# MCU.net
KiCad netlist of a schematic drawn in Altium Designer
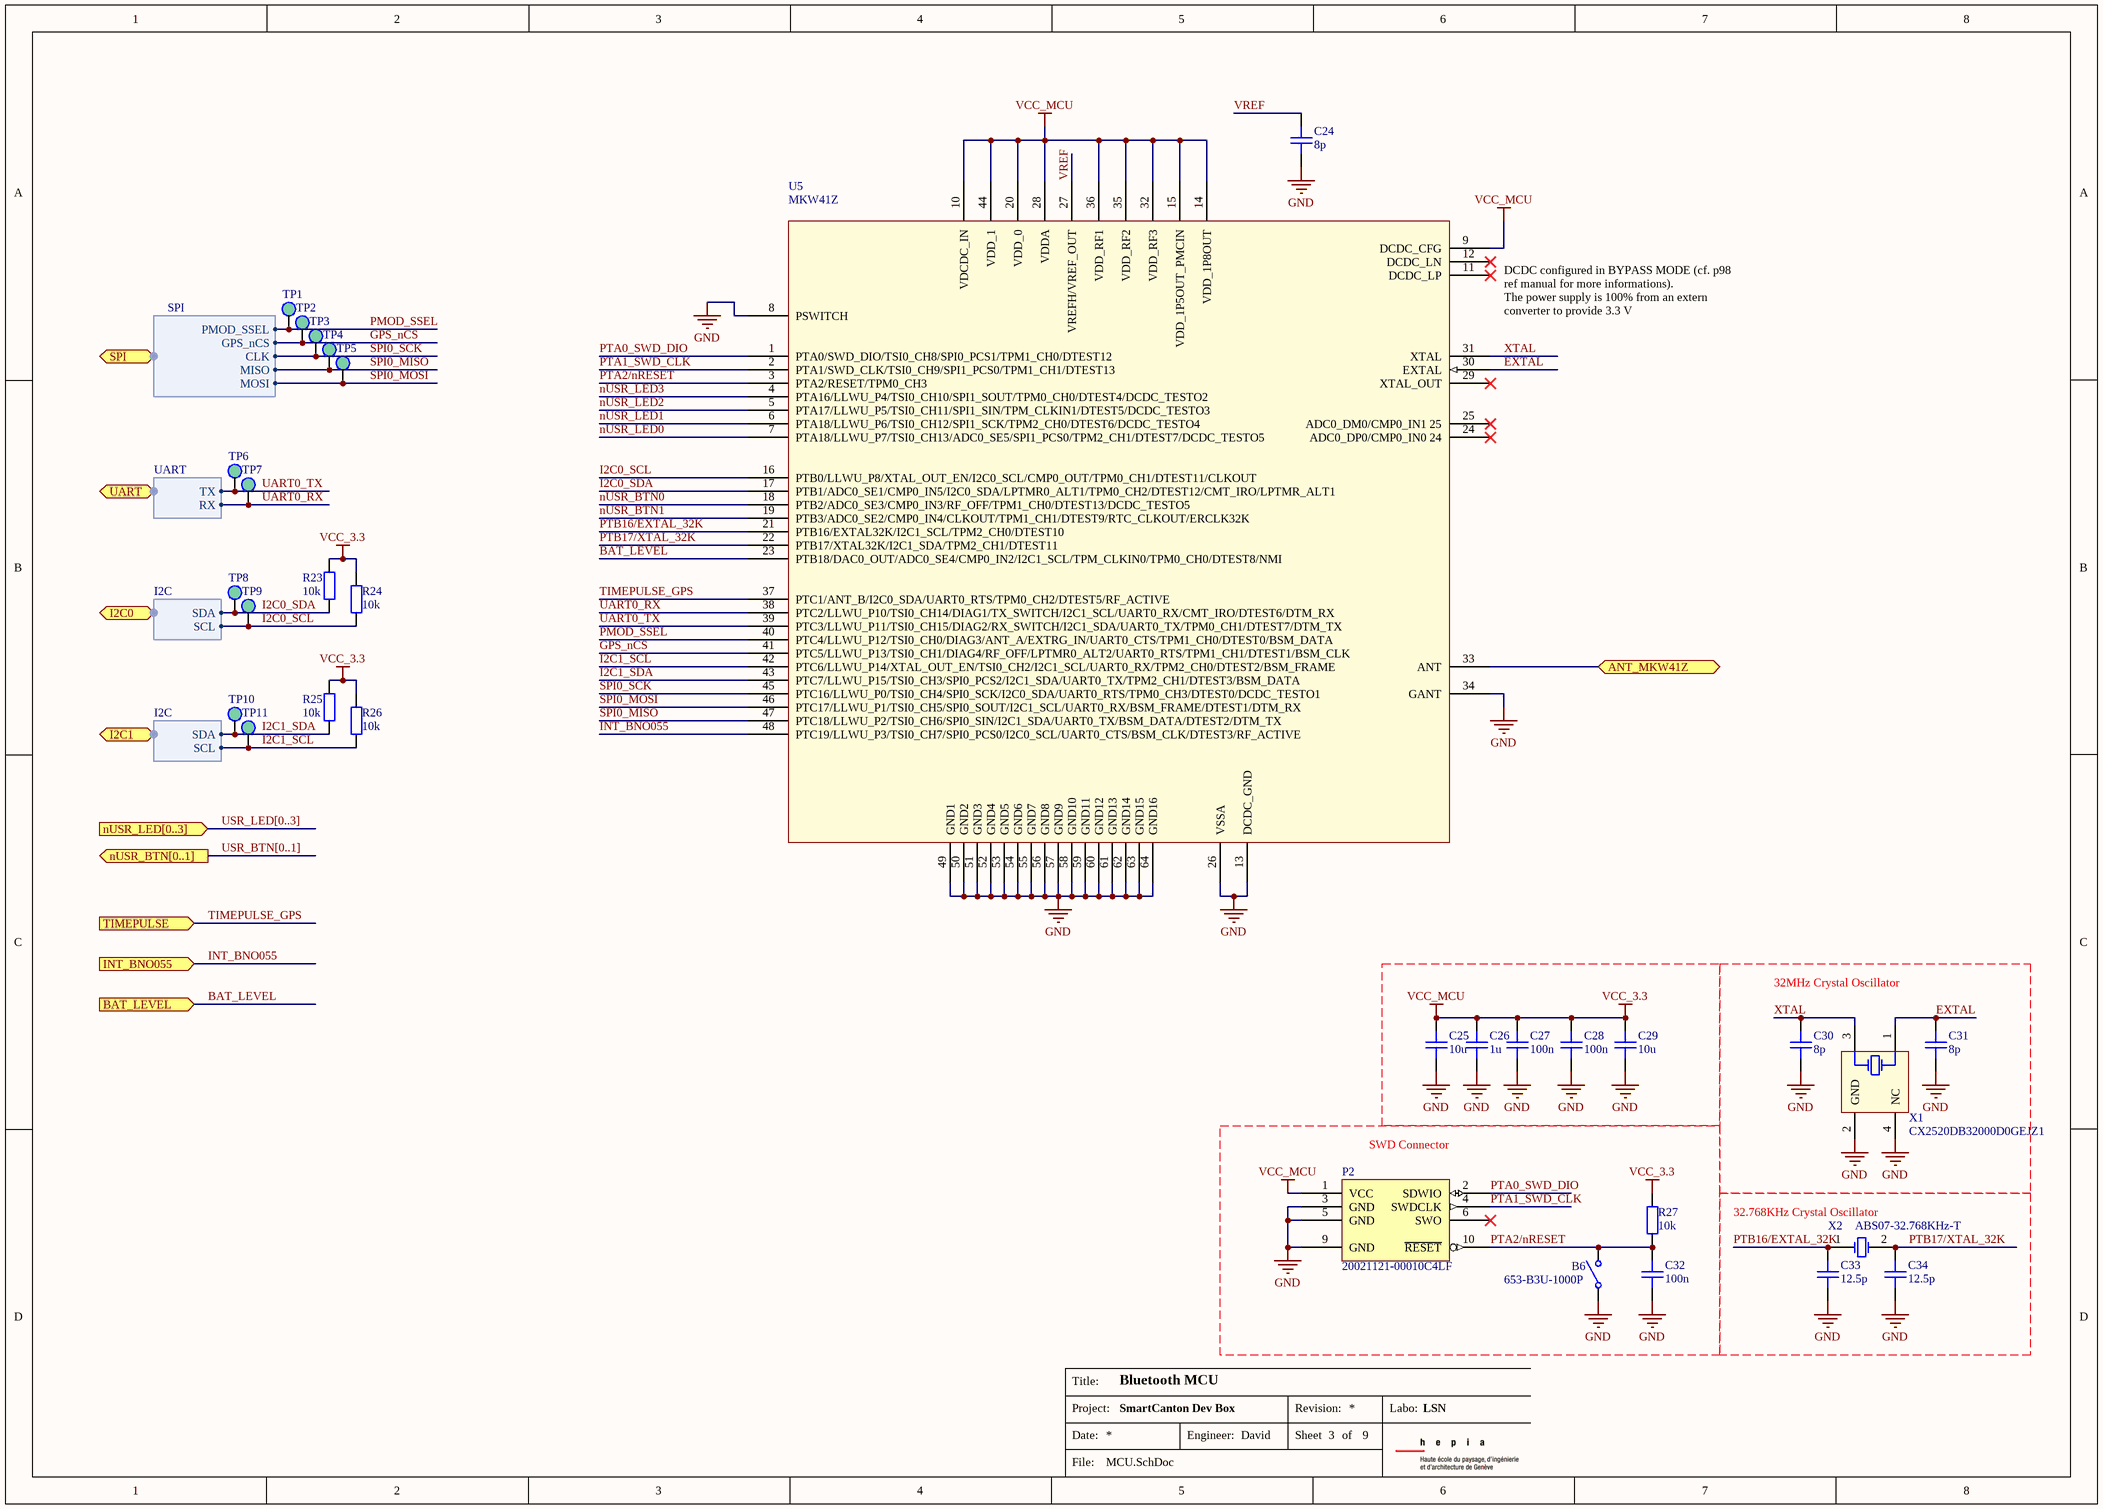
[diagram p0: MCU.SchDoc]

(export (version "E")
  (design (tool "Eeschema 10.0.6"))
  (components
    (comp (ref "B6")
      (value "653-B3U-1000P")
      (footprint "B3U-1000P")
      (fields (field (name "SUPPLIER PART NUMBER 1") "653-B3U-1000P"))
      (libsource (lib "eSurf_handle") (part "PUSH_BUTTON"))
    )
    (comp (ref "C24")
      (value "8p")
      (footprint "CAPC1608X08")
      (description "MLCC Capacitor 1608")
      (libsource (lib "HEPIA Vault") (part "CMP-001-0010-A.3"))
    )
    (comp (ref "C25")
      (value "10u")
      (footprint "CAPC1608X08N")
      (description "MLCC Capacitor 1608")
      (libsource (lib "HEPIA Vault") (part "CMP-001-0010-A.1"))
    )
    (comp (ref "C26")
      (value "1u")
      (footprint "CAPC1608X08N")
      (description "MLCC Capacitor 1608")
      (libsource (lib "HEPIA Vault") (part "CMP-001-0010-A.1"))
    )
    (comp (ref "C27")
      (value "100n")
      (footprint "CAPC1608X08N")
      (description "MLCC Capacitor 1608")
      (libsource (lib "HEPIA Vault") (part "CMP-001-0010-A.1"))
    )
    (comp (ref "C28")
      (value "100n")
      (footprint "CAPC1608X08N")
      (description "MLCC Capacitor 1608")
      (libsource (lib "HEPIA Vault") (part "CMP-001-0010-A.1"))
    )
    (comp (ref "C29")
      (value "10u")
      (footprint "CAPC1608X08N")
      (description "MLCC Capacitor 1608")
      (libsource (lib "HEPIA Vault") (part "CMP-001-0010-A.1"))
    )
    (comp (ref "C30")
      (value "8p")
      (footprint "CAPC1608X08")
      (description "MLCC Capacitor 1608")
      (libsource (lib "HEPIA Vault") (part "CMP-001-0010-A.3"))
    )
    (comp (ref "C31")
      (value "8p")
      (footprint "CAPC1608X08")
      (description "MLCC Capacitor 1608")
      (libsource (lib "HEPIA Vault") (part "CMP-001-0010-A.3"))
    )
    (comp (ref "C32")
      (value "100n")
      (footprint "CAPC1608X08")
      (description "MLCC Capacitor 1608")
      (libsource (lib "HEPIA Vault") (part "Capacitor"))
    )
    (comp (ref "C33")
      (value "12.5p")
      (footprint "CAPC1608X08")
      (description "MLCC Capacitor 1608")
      (libsource (lib "HEPIA Vault") (part "CMP-001-0010-A.3"))
    )
    (comp (ref "C34")
      (value "12.5p")
      (footprint "CAPC1608X08")
      (description "MLCC Capacitor 1608")
      (libsource (lib "HEPIA Vault") (part "CMP-001-0010-A.3"))
    )
    (comp (ref "P2")
      (value "20021121-00010C4LF")
      (footprint "PCBComponent")
      (description "Minitek127®  :  1.27x1.27MM BTB, HEADER UNSHROUDED, SMT, 10 POSITIONS")
      (libsource (lib "HEPIA Vault") (part "ARM-10-SWD"))
    )
    (comp (ref "R23")
      (value "10k")
      (footprint "RESC1608X06")
      (description "1608 resistor")
      (libsource (lib "HEPIA Vault") (part "CMP-001-0005-A.4"))
    )
    (comp (ref "R24")
      (value "10k")
      (footprint "RESC1608X06")
      (description "1608 resistor")
      (libsource (lib "HEPIA Vault") (part "CMP-001-0005-A.4"))
    )
    (comp (ref "R25")
      (value "10k")
      (footprint "RESC1608X06")
      (description "1608 resistor")
      (libsource (lib "HEPIA Vault") (part "CMP-001-0005-A.4"))
    )
    (comp (ref "R26")
      (value "10k")
      (footprint "RESC1608X06")
      (description "1608 resistor")
      (libsource (lib "HEPIA Vault") (part "CMP-001-0005-A.4"))
    )
    (comp (ref "R27")
      (value "10k")
      (footprint "RESC1608X06")
      (description "1608 resistor")
      (libsource (lib "") (part "CMP-001-0005-A.4_1"))
    )
    (comp (ref "TP1")
      (value "5015")
      (footprint "5015")
      (description "Circuit Board Hardware - PCB MINI SMT TEST POINT")
      (libsource (lib "HEPIA Vault") (part "TP"))
    )
    (comp (ref "TP2")
      (value "5015")
      (footprint "5015")
      (description "Circuit Board Hardware - PCB MINI SMT TEST POINT")
      (libsource (lib "HEPIA Vault") (part "TP"))
    )
    (comp (ref "TP3")
      (value "5015")
      (footprint "5015")
      (description "Circuit Board Hardware - PCB MINI SMT TEST POINT")
      (libsource (lib "HEPIA Vault") (part "TP"))
    )
    (comp (ref "TP4")
      (value "5015")
      (footprint "5015")
      (description "Circuit Board Hardware - PCB MINI SMT TEST POINT")
      (libsource (lib "HEPIA Vault") (part "TP"))
    )
    (comp (ref "TP5")
      (value "5015")
      (footprint "5015")
      (description "Circuit Board Hardware - PCB MINI SMT TEST POINT")
      (libsource (lib "HEPIA Vault") (part "TP"))
    )
    (comp (ref "TP6")
      (value "5015")
      (footprint "5015")
      (description "Circuit Board Hardware - PCB MINI SMT TEST POINT")
      (libsource (lib "HEPIA Vault") (part "TP"))
    )
    (comp (ref "TP7")
      (value "5015")
      (footprint "5015")
      (description "Circuit Board Hardware - PCB MINI SMT TEST POINT")
      (libsource (lib "HEPIA Vault") (part "TP"))
    )
    (comp (ref "TP8")
      (value "5015")
      (footprint "5015")
      (description "Circuit Board Hardware - PCB MINI SMT TEST POINT")
      (libsource (lib "HEPIA Vault") (part "CMP-001-0108-A.3"))
    )
    (comp (ref "TP9")
      (value "5015")
      (footprint "5015")
      (description "Circuit Board Hardware - PCB MINI SMT TEST POINT")
      (libsource (lib "HEPIA Vault") (part "CMP-001-0108-A.3"))
    )
    (comp (ref "TP10")
      (value "5015")
      (footprint "5015")
      (description "Circuit Board Hardware - PCB MINI SMT TEST POINT")
      (libsource (lib "HEPIA Vault") (part "CMP-001-0108-A.3"))
    )
    (comp (ref "TP11")
      (value "5015")
      (footprint "5015")
      (description "Circuit Board Hardware - PCB MINI SMT TEST POINT")
      (libsource (lib "HEPIA Vault") (part "CMP-001-0108-A.3"))
    )
    (comp (ref "U5")
      (value "MKW41Z")
      (footprint "QFN50P700X700X80_HS-49M")
      (libsource (lib "HEPIA Vault") (part "CMP-001-0100-A.1"))
    )
    (comp (ref "X1")
      (value "CX2520DB32000D0GEJZ1")
      (footprint "AVX-CX2520DB32000D0GEJZ1-4_V")
      (description "Crystal, 32 MHz, 8 pF, -10 to 70 degC, Surface Mount 2.5 x 2.0 mm")
      (fields (field (name "MANUFACTURER") "Kyocera"))
      (libsource (lib "Altium Content Vault") (part "AVX-CX2520DB32000D0GEJZ1-4"))
    )
    (comp (ref "X2")
      (value "ABS07-32.768KHz-T")
      (footprint "ABRA-ABS07-2_V")
      (description "Crystal, 32.768 kHz, 12.5 pF, -40 to 85 degC, SMD Low Profile 3.2 x 1.5 x 0.9 mm, Tape and Reel")
      (fields (field (name "MANUFACTURER") "Abracon"))
      (libsource (lib "Altium Content Vault") (part "CMP-0447-00001-2"))
    )
  )
  (nets
    (net (code "10") (name "/ANT_MKW41Z") (class "Default")
      (node (ref "U5") (pin "33") (pinfunction "ANT_33") (pintype "passive"))
    )
    (net (code "11") (name "/BAT_LEVEL") (class "Default")
      (node (ref "U5") (pin "23") (pinfunction "PTB18/DAC0_OUT/ADC0_SE4/CMP0_IN2/I2C1_SCL/TPM_CLKIN0/TPM0_CH0/DTEST8/NMI_23") (pintype "passive"))
    )
    (net (code "12") (name "/EXTAL") (class "Default")
      (node (ref "C31") (pin "2") (pinfunction "2_2") (pintype "passive"))
      (node (ref "U5") (pin "30") (pinfunction "EXTAL_30") (pintype "input"))
      (node (ref "X1") (pin "1") (pinfunction "HOT_1") (pintype "passive"))
    )
    (net (code "13") (name "/GPS_nCS") (class "Default")
      (node (ref "TP2") (pin "1") (pinfunction "TP_1") (pintype "passive"))
      (node (ref "U5") (pin "41") (pinfunction "PTC5/LLWU_P13/TSI0_CH1/DIAG4/RF_OFF/LPTMR0_ALT2/UART0_RTS/TPM1_CH1/DTEST1/BSM_CLK_41") (pintype "passive"))
    )
    (net (code "14") (name "/I2C0_SCL") (class "Default")
      (node (ref "R24") (pin "1") (pinfunction "1_1") (pintype "passive"))
      (node (ref "TP9") (pin "1") (pinfunction "TP_1") (pintype "passive"))
      (node (ref "U5") (pin "16") (pinfunction "PTB0/LLWU_P8/XTAL_OUT_EN/I2C0_SCL/CMP0_OUT/TPM0_CH1/DTEST11/CLKOUT_16") (pintype "passive"))
    )
    (net (code "15") (name "/I2C0_SDA") (class "Default")
      (node (ref "R23") (pin "1") (pinfunction "1_1") (pintype "passive"))
      (node (ref "TP8") (pin "1") (pinfunction "TP_1") (pintype "passive"))
      (node (ref "U5") (pin "17") (pinfunction "PTB1/ADC0_SE1/CMP0_IN5/I2C0_SDA/LPTMR0_ALT1/TPM0_CH2/DTEST12/CMT_IRO/LPTMR_ALT1_17") (pintype "passive"))
    )
    (net (code "16") (name "/I2C1_SCL") (class "Default")
      (node (ref "R26") (pin "1") (pinfunction "1_1") (pintype "passive"))
      (node (ref "TP11") (pin "1") (pinfunction "TP_1") (pintype "passive"))
      (node (ref "U5") (pin "42") (pinfunction "PTC6/LLWU_P14/XTAL_OUT_EN/TSI0_CH2/I2C1_SCL/UART0_RX/TPM2_CH0/DTEST2/BSM_FRAME_42") (pintype "passive"))
    )
    (net (code "17") (name "/I2C1_SDA") (class "Default")
      (node (ref "R25") (pin "1") (pinfunction "1_1") (pintype "passive"))
      (node (ref "TP10") (pin "1") (pinfunction "TP_1") (pintype "passive"))
      (node (ref "U5") (pin "43") (pinfunction "PTC7/LLWU_P15/TSI0_CH3/SPI0_PCS2/I2C1_SDA/UART0_TX/TPM2_CH1/DTEST3/BSM_DATA_43") (pintype "passive"))
    )
    (net (code "18") (name "/INT_BNO055") (class "Default")
      (node (ref "U5") (pin "48") (pinfunction "PTC19/LLWU_P3/TSI0_CH7/SPI0_PCS0/I2C0_SCL/UART0_CTS/BSM_CLK/DTEST3/RF_ACTIVE_48") (pintype "passive"))
    )
    (net (code "19") (name "/PMOD_SSEL") (class "Default")
      (node (ref "TP1") (pin "1") (pinfunction "TP_1") (pintype "passive"))
      (node (ref "U5") (pin "40") (pinfunction "PTC4/LLWU_P12/TSI0_CH0/DIAG3/ANT_A/EXTRG_IN/UART0_CTS/TPM1_CH0/DTEST0/BSM_DATA_40") (pintype "passive"))
    )
    (net (code "20") (name "/PTA0_SWD_DIO") (class "Default")
      (node (ref "P2") (pin "2") (pinfunction "SDWIO_2") (pintype "bidirectional"))
      (node (ref "U5") (pin "1") (pinfunction "PTA0/SWD_DIO/TSI0_CH8/SPI0_PCS1/TPM1_CH0/DTEST12_1") (pintype "passive"))
    )
    (net (code "21") (name "/PTA1_SWD_CLK") (class "Default")
      (node (ref "P2") (pin "4") (pinfunction "SWDCLK_4") (pintype "output"))
      (node (ref "U5") (pin "2") (pinfunction "PTA1/SWD_CLK/TSI0_CH9/SPI1_PCS0/TPM1_CH1/DTEST13_2") (pintype "passive"))
    )
    (net (code "22") (name "/PTA2{slash}nRESET") (class "Default")
      (node (ref "B6") (pin "2") (pinfunction "2_2") (pintype "passive"))
      (node (ref "C32") (pin "2") (pinfunction "2_2") (pintype "passive"))
      (node (ref "P2") (pin "10") (pinfunction "~{RESET}_10") (pintype "output"))
      (node (ref "R27") (pin "2") (pinfunction "2_2") (pintype "passive"))
      (node (ref "U5") (pin "3") (pinfunction "PTA2/RESET/TPM0_CH3_3") (pintype "passive"))
    )
    (net (code "23") (name "/PTB16{slash}EXTAL_32K") (class "Default")
      (node (ref "C33") (pin "2") (pinfunction "2_2") (pintype "passive"))
      (node (ref "U5") (pin "21") (pinfunction "PTB16/EXTAL32K/I2C1_SCL/TPM2_CH0/DTEST10_21") (pintype "passive"))
      (node (ref "X2") (pin "1") (pinfunction "X1_1") (pintype "passive"))
    )
    (net (code "24") (name "/PTB17{slash}XTAL_32K") (class "Default")
      (node (ref "C34") (pin "2") (pinfunction "2_2") (pintype "passive"))
      (node (ref "U5") (pin "22") (pinfunction "PTB17/XTAL32K/I2C1_SDA/TPM2_CH1/DTEST11_22") (pintype "passive"))
      (node (ref "X2") (pin "2") (pinfunction "X2_2") (pintype "passive"))
    )
    (net (code "25") (name "/SPI0_MISO") (class "Default")
      (node (ref "TP4") (pin "1") (pinfunction "TP_1") (pintype "passive"))
      (node (ref "U5") (pin "47") (pinfunction "PTC18/LLWU_P2/TSI0_CH6/SPI0_SIN/I2C1_SDA/UART0_TX/BSM_DATA/DTEST2/DTM_TX_47") (pintype "passive"))
    )
    (net (code "26") (name "/SPI0_MOSI") (class "Default")
      (node (ref "TP5") (pin "1") (pinfunction "TP_1") (pintype "passive"))
      (node (ref "U5") (pin "46") (pinfunction "PTC17/LLWU_P1/TSI0_CH5/SPI0_SOUT/I2C1_SCL/UART0_RX/BSM_FRAME/DTEST1/DTM_RX_46") (pintype "passive"))
    )
    (net (code "27") (name "/SPI0_SCK") (class "Default")
      (node (ref "TP3") (pin "1") (pinfunction "TP_1") (pintype "passive"))
      (node (ref "U5") (pin "45") (pinfunction "PTC16/LLWU_P0/TSI0_CH4/SPI0_SCK/I2C0_SDA/UART0_RTS/TPM0_CH3/DTEST0/DCDC_TESTO1_45") (pintype "passive"))
    )
    (net (code "28") (name "/TIMEPULSE_GPS") (class "Default")
      (node (ref "U5") (pin "37") (pinfunction "PTC1/ANT_B/I2C0_SDA/UART0_RTS/TPM0_CH2/DTEST5/RF_ACTIVE_37") (pintype "passive"))
    )
    (net (code "29") (name "/UART0_RX") (class "Default")
      (node (ref "TP7") (pin "1") (pinfunction "TP_1") (pintype "passive"))
      (node (ref "U5") (pin "38") (pinfunction "PTC2/LLWU_P10/TSI0_CH14/DIAG1/TX_SWITCH/I2C1_SCL/UART0_RX/CMT_IRO/DTEST6/DTM_RX_38") (pintype "passive"))
    )
    (net (code "30") (name "/UART0_TX") (class "Default")
      (node (ref "TP6") (pin "1") (pinfunction "TP_1") (pintype "passive"))
      (node (ref "U5") (pin "39") (pinfunction "PTC3/LLWU_P11/TSI0_CH15/DIAG2/RX_SWITCH/I2C1_SDA/UART0_TX/TPM0_CH1/DTEST7/DTM_TX_39") (pintype "passive"))
    )
    (net (code "31") (name "/USR_BTN0") (class "Default")
      (node (ref "U5") (pin "18") (pinfunction "PTB2/ADC0_SE3/CMP0_IN3/RF_OFF/TPM1_CH0/DTEST13/DCDC_TESTO5_18") (pintype "passive"))
    )
    (net (code "32") (name "/USR_BTN1") (class "Default")
      (node (ref "U5") (pin "19") (pinfunction "PTB3/ADC0_SE2/CMP0_IN4/CLKOUT/TPM1_CH1/DTEST9/RTC_CLKOUT/ERCLK32K_19") (pintype "passive"))
    )
    (net (code "34") (name "/USR_LED0") (class "Default")
      (node (ref "U5") (pin "7") (pinfunction "PTA18/LLWU_P7/TSI0_CH13/ADC0_SE5/SPI1_PCS0/TPM2_CH1/DTEST7/DCDC_TESTO5_7") (pintype "passive"))
    )
    (net (code "35") (name "/USR_LED1") (class "Default")
      (node (ref "U5") (pin "6") (pinfunction "PTA18/LLWU_P6/TSI0_CH12/SPI1_SCK/TPM2_CH0/DTEST6/DCDC_TESTO4_6") (pintype "passive"))
    )
    (net (code "36") (name "/USR_LED2") (class "Default")
      (node (ref "U5") (pin "5") (pinfunction "PTA17/LLWU_P5/TSI0_CH11/SPI1_SIN/TPM_CLKIN1/DTEST5/DCDC_TESTO3_5") (pintype "passive"))
    )
    (net (code "37") (name "/USR_LED3") (class "Default")
      (node (ref "U5") (pin "4") (pinfunction "PTA16/LLWU_P4/TSI0_CH10/SPI1_SOUT/TPM0_CH0/DTEST4/DCDC_TESTO2_4") (pintype "passive"))
    )
    (net (code "39") (name "/VREF") (class "Default")
      (node (ref "C24") (pin "2") (pinfunction "2_2") (pintype "passive"))
      (node (ref "U5") (pin "27") (pinfunction "VREFH/VREF_OUT_27") (pintype "passive"))
    )
    (net (code "40") (name "/XTAL") (class "Default")
      (node (ref "C30") (pin "2") (pinfunction "2_2") (pintype "passive"))
      (node (ref "U5") (pin "31") (pinfunction "XTAL_31") (pintype "passive"))
      (node (ref "X1") (pin "3") (pinfunction "HOT_3") (pintype "passive"))
    )
    (net (code "44") (name "GND") (class "Default")
      (node (ref "B6") (pin "1") (pinfunction "1_1") (pintype "passive"))
      (node (ref "C24") (pin "1") (pinfunction "1_1") (pintype "passive"))
      (node (ref "C25") (pin "1") (pinfunction "1_1") (pintype "passive"))
      (node (ref "C26") (pin "1") (pinfunction "1_1") (pintype "passive"))
      (node (ref "C27") (pin "1") (pinfunction "1_1") (pintype "passive"))
      (node (ref "C28") (pin "1") (pinfunction "1_1") (pintype "passive"))
      (node (ref "C29") (pin "1") (pinfunction "1_1") (pintype "passive"))
      (node (ref "C30") (pin "1") (pinfunction "1_1") (pintype "passive"))
      (node (ref "C31") (pin "1") (pinfunction "1_1") (pintype "passive"))
      (node (ref "C32") (pin "1") (pinfunction "1_1") (pintype "passive"))
      (node (ref "C33") (pin "1") (pinfunction "1_1") (pintype "passive"))
      (node (ref "C34") (pin "1") (pinfunction "1_1") (pintype "passive"))
      (node (ref "P2") (pin "3") (pinfunction "GND_3") (pintype "power_in"))
      (node (ref "P2") (pin "5") (pinfunction "GND_5") (pintype "power_in"))
      (node (ref "P2") (pin "9") (pinfunction "GND_9") (pintype "power_in"))
      (node (ref "U5") (pin "13") (pinfunction "DCDC_GND_13") (pintype "passive"))
      (node (ref "U5") (pin "26") (pinfunction "VSSA_26") (pintype "passive"))
      (node (ref "U5") (pin "34") (pinfunction "GANT_34") (pintype "passive"))
      (node (ref "U5") (pin "49") (pinfunction "GND1_49") (pintype "passive"))
      (node (ref "U5") (pin "50") (pinfunction "GND2_50") (pintype "passive"))
      (node (ref "U5") (pin "51") (pinfunction "GND3_51") (pintype "passive"))
      (node (ref "U5") (pin "52") (pinfunction "GND4_52") (pintype "passive"))
      (node (ref "U5") (pin "53") (pinfunction "GND5_53") (pintype "passive"))
      (node (ref "U5") (pin "54") (pinfunction "GND6_54") (pintype "passive"))
      (node (ref "U5") (pin "55") (pinfunction "GND7_55") (pintype "passive"))
      (node (ref "U5") (pin "56") (pinfunction "GND8_56") (pintype "passive"))
      (node (ref "U5") (pin "57") (pinfunction "GND9_57") (pintype "passive"))
      (node (ref "U5") (pin "58") (pinfunction "GND10_58") (pintype "passive"))
      (node (ref "U5") (pin "59") (pinfunction "GND11_59") (pintype "passive"))
      (node (ref "U5") (pin "60") (pinfunction "GND12_60") (pintype "passive"))
      (node (ref "U5") (pin "61") (pinfunction "GND13_61") (pintype "passive"))
      (node (ref "U5") (pin "62") (pinfunction "GND14_62") (pintype "passive"))
      (node (ref "U5") (pin "63") (pinfunction "GND15_63") (pintype "passive"))
      (node (ref "U5") (pin "64") (pinfunction "GND16_64") (pintype "passive"))
      (node (ref "U5") (pin "8") (pinfunction "PSWITCH_8") (pintype "passive"))
      (node (ref "X1") (pin "2") (pinfunction "GND_2") (pintype "power_in"))
      (node (ref "X1") (pin "4") (pinfunction "NC_4") (pintype "passive"))
    )
    (net (code "45") (name "VCC_3.3") (class "Default")
      (node (ref "C25") (pin "2") (pinfunction "2_2") (pintype "passive"))
      (node (ref "C26") (pin "2") (pinfunction "2_2") (pintype "passive"))
      (node (ref "C27") (pin "2") (pinfunction "2_2") (pintype "passive"))
      (node (ref "C28") (pin "2") (pinfunction "2_2") (pintype "passive"))
      (node (ref "C29") (pin "2") (pinfunction "2_2") (pintype "passive"))
      (node (ref "P2") (pin "1") (pinfunction "VCC_1") (pintype "power_in"))
      (node (ref "R23") (pin "2") (pinfunction "2_2") (pintype "passive"))
      (node (ref "R24") (pin "2") (pinfunction "2_2") (pintype "passive"))
      (node (ref "R25") (pin "2") (pinfunction "2_2") (pintype "passive"))
      (node (ref "R26") (pin "2") (pinfunction "2_2") (pintype "passive"))
      (node (ref "R27") (pin "1") (pinfunction "1_1") (pintype "passive"))
      (node (ref "U5") (pin "10") (pinfunction "VDCDC_IN_10") (pintype "passive"))
      (node (ref "U5") (pin "14") (pinfunction "VDD_1P8OUT_14") (pintype "passive"))
      (node (ref "U5") (pin "15") (pinfunction "VDD_1P5OUT_PMCIN_15") (pintype "passive"))
      (node (ref "U5") (pin "20") (pinfunction "VDD_0_20") (pintype "passive"))
      (node (ref "U5") (pin "28") (pinfunction "VDDA_28") (pintype "passive"))
      (node (ref "U5") (pin "32") (pinfunction "VDD_RF3_32") (pintype "passive"))
      (node (ref "U5") (pin "35") (pinfunction "VDD_RF2_35") (pintype "passive"))
      (node (ref "U5") (pin "36") (pinfunction "VDD_RF1_36") (pintype "passive"))
      (node (ref "U5") (pin "44") (pinfunction "VDD_1_44") (pintype "passive"))
      (node (ref "U5") (pin "9") (pinfunction "DCDC_CFG_9") (pintype "passive"))
    )
    (net (code "46") (name "unconnected-(P2-SWO-Pad6)") (class "Default")
      (node (ref "P2") (pin "6") (pinfunction "SWO_6") (pintype "passive+no_connect"))
    )
    (net (code "47") (name "unconnected-(U5-ADC0_DM0{slash}CMP0_IN1_25-Pad25)") (class "Default")
      (node (ref "U5") (pin "25") (pinfunction "ADC0_DM0/CMP0_IN1_25_25") (pintype "passive+no_connect"))
    )
    (net (code "48") (name "unconnected-(U5-ADC0_DP0{slash}CMP0_IN0_24-Pad24)") (class "Default")
      (node (ref "U5") (pin "24") (pinfunction "ADC0_DP0/CMP0_IN0_24_24") (pintype "passive+no_connect"))
    )
    (net (code "49") (name "unconnected-(U5-DCDC_LN-Pad12)") (class "Default")
      (node (ref "U5") (pin "12") (pinfunction "DCDC_LN_12") (pintype "passive+no_connect"))
    )
    (net (code "50") (name "unconnected-(U5-DCDC_LP-Pad11)") (class "Default")
      (node (ref "U5") (pin "11") (pinfunction "DCDC_LP_11") (pintype "passive+no_connect"))
    )
    (net (code "51") (name "unconnected-(U5-XTAL_OUT-Pad29)") (class "Default")
      (node (ref "U5") (pin "29") (pinfunction "XTAL_OUT_29") (pintype "passive+no_connect"))
    )
  )
)
